# supply_interface.net
KiCad netlist of a schematic drawn in Altium Designer
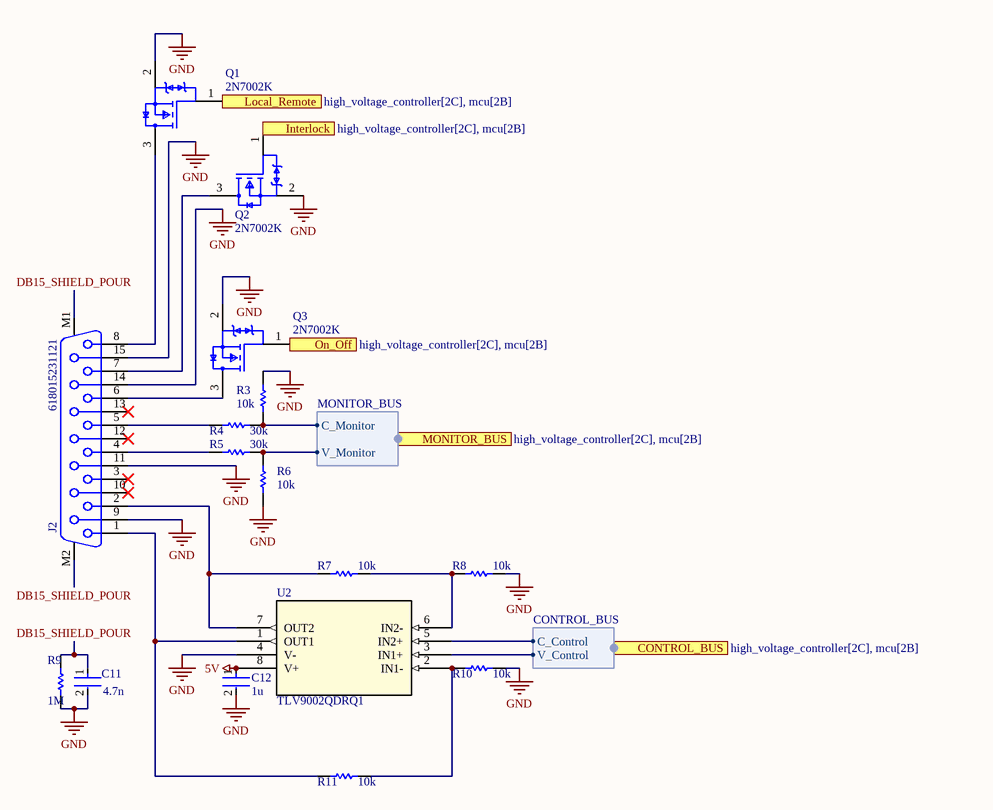
[diagram p0: supply_interface.SchDoc]

(export (version "E")
  (design (tool "Eeschema 10.0.6"))
  (components
    (comp (ref "C11")
      (value "4.7n")
      (footprint "C_IM 0805")
      (description "Cap Ceramic 0.0047uF 1000V X7R 10% Pad SMD 0805 125C Automotive AEC-Q200 Medical T/R")
      (fields
        (field (name "MANUFACTURER") "Yageo Group")
        (field (name "MANUFACTURER PART NUMBER") "C0805C472KDRACAUTO")
      )
      (libsource (lib "Schlib1") (part "C0805C472KDRACAUTO"))
    )
    (comp (ref "C12")
      (value "1u")
      (footprint "C_IM 0603")
      (description "16V 1uF X7R ±10% 0603 Multilayer Ceramic Capacitors MLCC - SMD/SMT ROHS")
      (fields
        (field (name "MANUFACTURER") "Yageo Group")
        (field (name "MANUFACTURER PART NUMBER") "CC0603KRX7R7BB105")
      )
      (libsource (lib "high_voltage_controller") (part "CC0603KRX7R7BB105"))
    )
    (comp (ref "J2")
      (value "618015231121")
      (footprint "618015231121")
      (description "15 Way Right Angle Through Hole Pcb D-sub Connector Socket, 2.77MM, 2.84MM Pitch")
      (fields (field (name "MANUFACTURER") "Wurth Elektronik"))
      (libsource (lib "Schlib1") (part "618015231121"))
    )
    (comp (ref "Q1")
      (value "2N7002K")
      (footprint "SOT-23-3")
      (description "Mosfet N-ch 60V 300MA SOT23 / Trans Mosfet N-ch 60V 0.3A 3-PIN SOT-23 T/r")
      (fields (field (name "MANUFACTURER") "onsemi") (field (name "VOLTAGE") "60V"))
      (libsource (lib "Schlib1") (part "2N7002K"))
    )
    (comp (ref "Q2")
      (value "2N7002K")
      (footprint "SOT-23-3")
      (description "Mosfet N-ch 60V 300MA SOT23 / Trans Mosfet N-ch 60V 0.3A 3-PIN SOT-23 T/r")
      (fields (field (name "MANUFACTURER") "onsemi") (field (name "VOLTAGE") "60V"))
      (libsource (lib "Schlib1") (part "2N7002K"))
    )
    (comp (ref "Q3")
      (value "2N7002K")
      (footprint "SOT-23-3")
      (description "Mosfet N-ch 60V 300MA SOT23 / Trans Mosfet N-ch 60V 0.3A 3-PIN SOT-23 T/r")
      (fields (field (name "MANUFACTURER") "onsemi") (field (name "VOLTAGE") "60V"))
      (libsource (lib "Schlib1") (part "2N7002K"))
    )
    (comp (ref "R3")
      (value "10k")
      (footprint "R_IM 0805")
      (description "Res General Purpose Thick Film 0805 10k Ohm 1% 1/8W ±100ppm/°C Ceramic Paper T/R")
      (fields
        (field (name "MANUFACTURER") "Yageo Group")
        (field (name "MANUFACTURER PART NUMBER") "RC0805FR-0710KL")
      )
      (libsource (lib "high_voltage_controller") (part "RC0805FR-0710KL"))
    )
    (comp (ref "R4")
      (value "30k")
      (footprint "R_IM 0805")
      (description "125mW Thick Film Resistors 150V ±100ppm/℃ ±1% 30kΩ 0805 Chip Resistor - Surface Mount ROHS")
      (fields
        (field (name "MANUFACTURER") "Yageo Group")
        (field (name "MANUFACTURER PART NUMBER") "RC0805FR-0730KL")
      )
      (libsource (lib "high_voltage_controller") (part "RC0805FR-0730KL"))
    )
    (comp (ref "R5")
      (value "30k")
      (footprint "R_IM 0805")
      (description "125mW Thick Film Resistors 150V ±100ppm/℃ ±1% 30kΩ 0805 Chip Resistor - Surface Mount ROHS")
      (fields
        (field (name "MANUFACTURER") "Yageo Group")
        (field (name "MANUFACTURER PART NUMBER") "RC0805FR-0730KL")
      )
      (libsource (lib "high_voltage_controller") (part "RC0805FR-0730KL"))
    )
    (comp (ref "R6")
      (value "10k")
      (footprint "R_IM 0805")
      (description "Res General Purpose Thick Film 0805 10k Ohm 1% 1/8W ±100ppm/°C Ceramic Paper T/R")
      (fields
        (field (name "MANUFACTURER") "Yageo Group")
        (field (name "MANUFACTURER PART NUMBER") "RC0805FR-0710KL")
      )
      (libsource (lib "high_voltage_controller") (part "RC0805FR-0710KL"))
    )
    (comp (ref "R7")
      (value "10k")
      (footprint "R_IM 0805")
      (description "Res General Purpose Thick Film 0805 10k Ohm 1% 1/8W ±100ppm/°C Ceramic Paper T/R")
      (fields
        (field (name "MANUFACTURER") "Yageo Group")
        (field (name "MANUFACTURER PART NUMBER") "RC0805FR-0710KL")
      )
      (libsource (lib "Schlib1") (part "RC0805FR-0710KL"))
    )
    (comp (ref "R8")
      (value "10k")
      (footprint "R_IM 0805")
      (description "Res General Purpose Thick Film 0805 10k Ohm 1% 1/8W ±100ppm/°C Ceramic Paper T/R")
      (fields
        (field (name "MANUFACTURER") "Yageo Group")
        (field (name "MANUFACTURER PART NUMBER") "RC0805FR-0710KL")
      )
      (libsource (lib "Schlib1") (part "RC0805FR-0710KL"))
    )
    (comp (ref "R9")
      (value "1M")
      (footprint "R_IM 0805")
      (description "Res Thick Film 0603 1M Ohm 1% 0.1W(1/10W) ±100ppm/°C Pad SMD T/R / RES SMD 1M OHM 1% 1/10W 0603")
      (fields
        (field (name "MANUFACTURER") "Yageo Group")
        (field (name "MANUFACTURER PART NUMBER") "RC0603FR-071ML")
      )
      (libsource (lib "Schlib1") (part "RC0603FR-071ML"))
    )
    (comp (ref "R10")
      (value "10k")
      (footprint "R_IM 0805")
      (description "Res General Purpose Thick Film 0805 10k Ohm 1% 1/8W ±100ppm/°C Ceramic Paper T/R")
      (fields
        (field (name "MANUFACTURER") "Yageo Group")
        (field (name "MANUFACTURER PART NUMBER") "RC0805FR-0710KL")
      )
      (libsource (lib "Schlib1") (part "RC0805FR-0710KL"))
    )
    (comp (ref "R11")
      (value "10k")
      (footprint "R_IM 0805")
      (description "Res General Purpose Thick Film 0805 10k Ohm 1% 1/8W ±100ppm/°C Ceramic Paper T/R")
      (fields
        (field (name "MANUFACTURER") "Yageo Group")
        (field (name "MANUFACTURER PART NUMBER") "RC0805FR-0710KL")
      )
      (libsource (lib "Schlib1") (part "RC0805FR-0710KL"))
    )
    (comp (ref "U2")
      (value "TLV9002QDRQ1")
      (footprint "SOIC8_D_TEX")
      (description "IC OPAMP GP 2 CIRCUIT 8SOIC / General Purpose Amplifier 2 Circuit Rail-to-Rail 8-SOIC")
      (fields (field (name "MANUFACTURER") "Texas Instruments"))
      (libsource (lib "high_voltage_controller") (part "TLV9002QDRQ1"))
    )
  )
  (nets
    (net (code "3") (name "/C_Control") (class "Default")
      (node (ref "U2") (pin "5") (pinfunction "IN2+_5") (pintype "input"))
    )
    (net (code "4") (name "/C_Monitor") (class "Default")
      (node (ref "R3") (pin "1") (pinfunction "1_1") (pintype "passive"))
      (node (ref "R4") (pin "2") (pinfunction "2_2") (pintype "passive"))
    )
    (net (code "5") (name "/DB15_SHIELD_POUR") (class "Default")
      (node (ref "C11") (pin "1") (pinfunction "1_1") (pintype "passive"))
      (node (ref "J2") (pin "M1") (pinfunction "M1_M1") (pintype "passive"))
      (node (ref "J2") (pin "M2") (pinfunction "M2_M2") (pintype "passive"))
      (node (ref "R9") (pin "2") (pinfunction "2_2") (pintype "passive"))
    )
    (net (code "6") (name "/Interlock") (class "Default")
      (node (ref "Q2") (pin "1") (pinfunction "Gate_1") (pintype "passive"))
    )
    (net (code "7") (name "/Local_Remote") (class "Default")
      (node (ref "Q1") (pin "1") (pinfunction "Gate_1") (pintype "passive"))
    )
    (net (code "8") (name "/On_Off") (class "Default")
      (node (ref "Q3") (pin "1") (pinfunction "Gate_1") (pintype "passive"))
    )
    (net (code "9") (name "/V_Control") (class "Default")
      (node (ref "U2") (pin "3") (pinfunction "IN1+_3") (pintype "input"))
    )
    (net (code "10") (name "/V_Monitor") (class "Default")
      (node (ref "R5") (pin "2") (pinfunction "2_2") (pintype "passive"))
      (node (ref "R6") (pin "2") (pinfunction "2_2") (pintype "passive"))
    )
    (net (code "13") (name "5V") (class "Default")
      (node (ref "C12") (pin "1") (pinfunction "1_1") (pintype "passive"))
      (node (ref "U2") (pin "8") (pinfunction "V+_8") (pintype "power_in"))
    )
    (net (code "14") (name "GND") (class "Default")
      (node (ref "C11") (pin "2") (pinfunction "2_2") (pintype "passive"))
      (node (ref "C12") (pin "2") (pinfunction "2_2") (pintype "passive"))
      (node (ref "J2") (pin "11") (pinfunction "11_11") (pintype "passive"))
      (node (ref "J2") (pin "14") (pinfunction "14_14") (pintype "passive"))
      (node (ref "J2") (pin "15") (pinfunction "15_15") (pintype "passive"))
      (node (ref "J2") (pin "9") (pinfunction "9_9") (pintype "passive"))
      (node (ref "Q1") (pin "2") (pinfunction "Source_2") (pintype "passive"))
      (node (ref "Q2") (pin "2") (pinfunction "Source_2") (pintype "passive"))
      (node (ref "Q3") (pin "2") (pinfunction "Source_2") (pintype "passive"))
      (node (ref "R10") (pin "2") (pinfunction "2_2") (pintype "passive"))
      (node (ref "R3") (pin "2") (pinfunction "2_2") (pintype "passive"))
      (node (ref "R6") (pin "1") (pinfunction "1_1") (pintype "passive"))
      (node (ref "R8") (pin "2") (pinfunction "2_2") (pintype "passive"))
      (node (ref "R9") (pin "1") (pinfunction "1_1") (pintype "passive"))
      (node (ref "U2") (pin "4") (pinfunction "V-_4") (pintype "passive"))
    )
    (net (code "15") (name "Net-(J2-Pad4)") (class "Default")
      (node (ref "J2") (pin "4") (pinfunction "4_4") (pintype "passive"))
      (node (ref "R5") (pin "1") (pinfunction "1_1") (pintype "passive"))
    )
    (net (code "16") (name "Net-(J2-Pad5)") (class "Default")
      (node (ref "J2") (pin "5") (pinfunction "5_5") (pintype "passive"))
      (node (ref "R4") (pin "1") (pinfunction "1_1") (pintype "passive"))
    )
    (net (code "17") (name "Net-(Q1-Drain)") (class "Default")
      (node (ref "J2") (pin "8") (pinfunction "8_8") (pintype "passive"))
      (node (ref "Q1") (pin "3") (pinfunction "Drain_3") (pintype "passive"))
    )
    (net (code "18") (name "Net-(Q2-Drain)") (class "Default")
      (node (ref "J2") (pin "7") (pinfunction "7_7") (pintype "passive"))
      (node (ref "Q2") (pin "3") (pinfunction "Drain_3") (pintype "passive"))
    )
    (net (code "19") (name "Net-(Q3-Drain)") (class "Default")
      (node (ref "J2") (pin "6") (pinfunction "6_6") (pintype "passive"))
      (node (ref "Q3") (pin "3") (pinfunction "Drain_3") (pintype "passive"))
    )
    (net (code "20") (name "Net-(U2-IN1-)") (class "Default")
      (node (ref "R10") (pin "1") (pinfunction "1_1") (pintype "passive"))
      (node (ref "R11") (pin "2") (pinfunction "2_2") (pintype "passive"))
      (node (ref "U2") (pin "2") (pinfunction "IN1-_2") (pintype "input"))
    )
    (net (code "21") (name "Net-(U2-IN2-)") (class "Default")
      (node (ref "R7") (pin "2") (pinfunction "2_2") (pintype "passive"))
      (node (ref "R8") (pin "1") (pinfunction "1_1") (pintype "passive"))
      (node (ref "U2") (pin "6") (pinfunction "IN2-_6") (pintype "input"))
    )
    (net (code "22") (name "Net-(U2-OUT1)") (class "Default")
      (node (ref "J2") (pin "1") (pinfunction "1_1") (pintype "passive"))
      (node (ref "R11") (pin "1") (pinfunction "1_1") (pintype "passive"))
      (node (ref "U2") (pin "1") (pinfunction "OUT1_1") (pintype "output"))
    )
    (net (code "23") (name "Net-(U2-OUT2)") (class "Default")
      (node (ref "J2") (pin "2") (pinfunction "2_2") (pintype "passive"))
      (node (ref "R7") (pin "1") (pinfunction "1_1") (pintype "passive"))
      (node (ref "U2") (pin "7") (pinfunction "OUT2_7") (pintype "output"))
    )
    (net (code "24") (name "unconnected-(J2-Pad3)") (class "Default")
      (node (ref "J2") (pin "3") (pinfunction "3_3") (pintype "passive+no_connect"))
    )
    (net (code "25") (name "unconnected-(J2-Pad10)") (class "Default")
      (node (ref "J2") (pin "10") (pinfunction "10_10") (pintype "passive+no_connect"))
    )
    (net (code "26") (name "unconnected-(J2-Pad12)") (class "Default")
      (node (ref "J2") (pin "12") (pinfunction "12_12") (pintype "passive+no_connect"))
    )
    (net (code "27") (name "unconnected-(J2-Pad13)") (class "Default")
      (node (ref "J2") (pin "13") (pinfunction "13_13") (pintype "passive+no_connect"))
    )
  )
)
